# Triton.net
KiCad netlist of a schematic drawn in Altium Designer
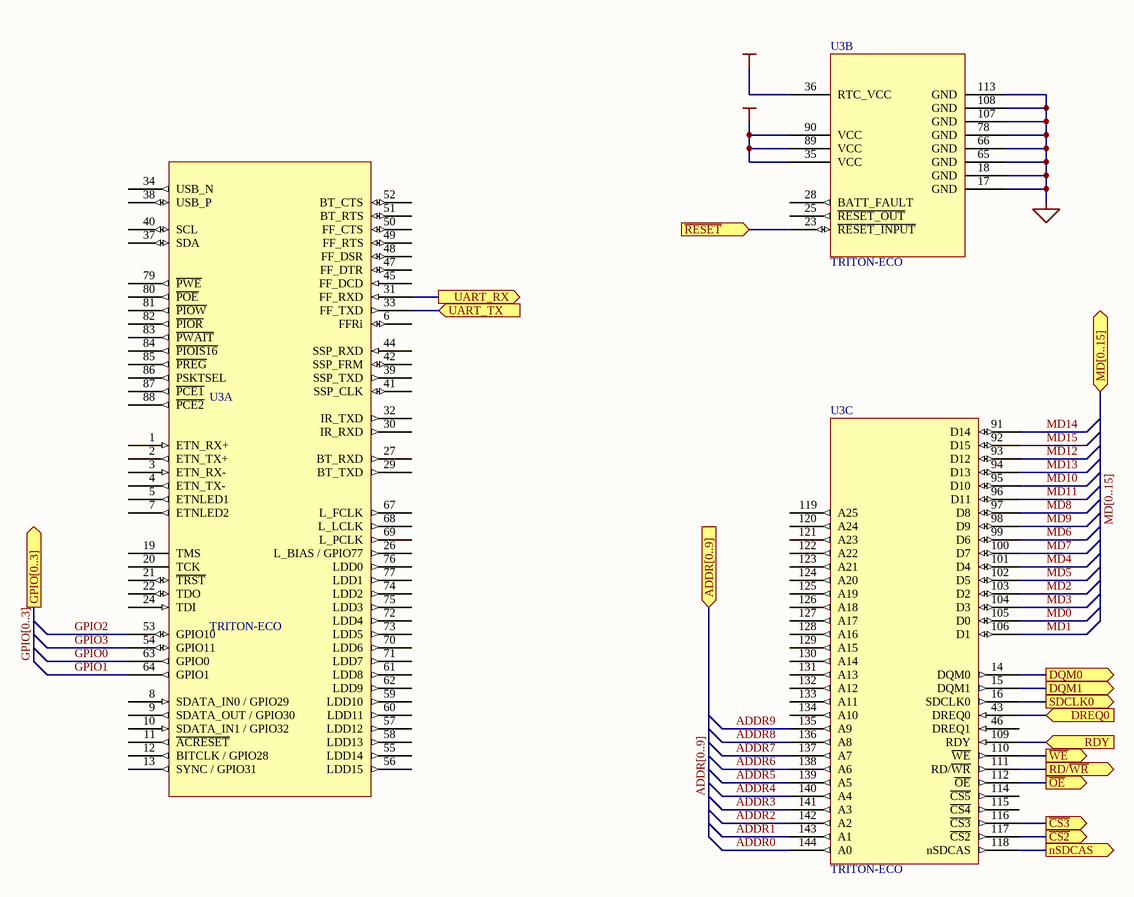
[diagram p0: Triton.SCHDOC]

(export (version "E")
  (design (tool "Eeschema 10.0.6"))
  (components
    (comp (ref "U3")
      (value "TRITON-ECO")
      (footprint "144-PIN SMT SODIMM")
      (description "Triton-ECO 400 MHz XScale DIMM")
      (libsource (lib "My devices") (part "TRITON_ECO"))
    )
  )
  (nets
    (net (code "1") (name "/ADDR0") (class "Default")
      (node (ref "U3") (pin "144") (pinfunction "A0_144") (pintype "output"))
    )
    (net (code "2") (name "/ADDR1") (class "Default")
      (node (ref "U3") (pin "143") (pinfunction "A1_143") (pintype "output"))
    )
    (net (code "3") (name "/ADDR2") (class "Default")
      (node (ref "U3") (pin "142") (pinfunction "A2_142") (pintype "output"))
    )
    (net (code "4") (name "/ADDR3") (class "Default")
      (node (ref "U3") (pin "141") (pinfunction "A3_141") (pintype "output"))
    )
    (net (code "5") (name "/ADDR4") (class "Default")
      (node (ref "U3") (pin "140") (pinfunction "A4_140") (pintype "output"))
    )
    (net (code "6") (name "/ADDR5") (class "Default")
      (node (ref "U3") (pin "139") (pinfunction "A5_139") (pintype "output"))
    )
    (net (code "7") (name "/ADDR6") (class "Default")
      (node (ref "U3") (pin "138") (pinfunction "A6_138") (pintype "output"))
    )
    (net (code "8") (name "/ADDR7") (class "Default")
      (node (ref "U3") (pin "137") (pinfunction "A7_137") (pintype "output"))
    )
    (net (code "9") (name "/ADDR8") (class "Default")
      (node (ref "U3") (pin "136") (pinfunction "A8_136") (pintype "output"))
    )
    (net (code "10") (name "/ADDR9") (class "Default")
      (node (ref "U3") (pin "135") (pinfunction "A9_135") (pintype "output"))
    )
    (net (code "12") (name "/DQM0") (class "Default")
      (node (ref "U3") (pin "14") (pinfunction "DQM0_14") (pintype "output"))
    )
    (net (code "13") (name "/DQM1") (class "Default")
      (node (ref "U3") (pin "15") (pinfunction "DQM1_15") (pintype "output"))
    )
    (net (code "14") (name "/DREQ0") (class "Default")
      (node (ref "U3") (pin "43") (pinfunction "DREQ0_43") (pintype "input"))
    )
    (net (code "15") (name "/GPIO0") (class "Default")
      (node (ref "U3") (pin "63") (pinfunction "GPIO0_63") (pintype "output"))
    )
    (net (code "16") (name "/GPIO1") (class "Default")
      (node (ref "U3") (pin "64") (pinfunction "GPIO1_64") (pintype "output"))
    )
    (net (code "17") (name "/GPIO2") (class "Default")
      (node (ref "U3") (pin "53") (pinfunction "GPIO10_53") (pintype "bidirectional"))
    )
    (net (code "18") (name "/GPIO3") (class "Default")
      (node (ref "U3") (pin "54") (pinfunction "GPIO11_54") (pintype "bidirectional"))
    )
    (net (code "20") (name "/MD0") (class "Default")
      (node (ref "U3") (pin "105") (pinfunction "D0_105") (pintype "bidirectional"))
    )
    (net (code "21") (name "/MD1") (class "Default")
      (node (ref "U3") (pin "106") (pinfunction "D1_106") (pintype "bidirectional"))
    )
    (net (code "22") (name "/MD2") (class "Default")
      (node (ref "U3") (pin "103") (pinfunction "D2_103") (pintype "bidirectional"))
    )
    (net (code "23") (name "/MD3") (class "Default")
      (node (ref "U3") (pin "104") (pinfunction "D3_104") (pintype "bidirectional"))
    )
    (net (code "24") (name "/MD4") (class "Default")
      (node (ref "U3") (pin "101") (pinfunction "D4_101") (pintype "bidirectional"))
    )
    (net (code "25") (name "/MD5") (class "Default")
      (node (ref "U3") (pin "102") (pinfunction "D5_102") (pintype "bidirectional"))
    )
    (net (code "26") (name "/MD6") (class "Default")
      (node (ref "U3") (pin "99") (pinfunction "D6_99") (pintype "bidirectional"))
    )
    (net (code "27") (name "/MD7") (class "Default")
      (node (ref "U3") (pin "100") (pinfunction "D7_100") (pintype "bidirectional"))
    )
    (net (code "28") (name "/MD8") (class "Default")
      (node (ref "U3") (pin "97") (pinfunction "D8_97") (pintype "bidirectional"))
    )
    (net (code "29") (name "/MD9") (class "Default")
      (node (ref "U3") (pin "98") (pinfunction "D9_98") (pintype "bidirectional"))
    )
    (net (code "30") (name "/MD10") (class "Default")
      (node (ref "U3") (pin "95") (pinfunction "D10_95") (pintype "bidirectional"))
    )
    (net (code "31") (name "/MD11") (class "Default")
      (node (ref "U3") (pin "96") (pinfunction "D11_96") (pintype "bidirectional"))
    )
    (net (code "32") (name "/MD12") (class "Default")
      (node (ref "U3") (pin "93") (pinfunction "D12_93") (pintype "bidirectional"))
    )
    (net (code "33") (name "/MD13") (class "Default")
      (node (ref "U3") (pin "94") (pinfunction "D13_94") (pintype "bidirectional"))
    )
    (net (code "34") (name "/MD14") (class "Default")
      (node (ref "U3") (pin "91") (pinfunction "D14_91") (pintype "bidirectional"))
    )
    (net (code "35") (name "/MD15") (class "Default")
      (node (ref "U3") (pin "92") (pinfunction "D15_92") (pintype "bidirectional"))
    )
    (net (code "37") (name "/RDY") (class "Default")
      (node (ref "U3") (pin "109") (pinfunction "RDY_109") (pintype "input"))
    )
    (net (code "38") (name "/RD{slash}~{WR}") (class "Default")
      (node (ref "U3") (pin "111") (pinfunction "RD/~{WR}_111") (pintype "output"))
    )
    (net (code "39") (name "/SDCLK0") (class "Default")
      (node (ref "U3") (pin "16") (pinfunction "SDCLK0_16") (pintype "output"))
    )
    (net (code "40") (name "/UART_RX") (class "Default")
      (node (ref "U3") (pin "31") (pinfunction "FF_RXD_31") (pintype "input"))
    )
    (net (code "41") (name "/UART_TX") (class "Default")
      (node (ref "U3") (pin "33") (pinfunction "FF_TXD_33") (pintype "output"))
    )
    (net (code "42") (name "/nSDCAS") (class "Default")
      (node (ref "U3") (pin "118") (pinfunction "nSDCAS_118") (pintype "output"))
    )
    (net (code "43") (name "/~{CS2}") (class "Default")
      (node (ref "U3") (pin "117") (pinfunction "~{CS2}_117") (pintype "output"))
    )
    (net (code "44") (name "/~{CS3}") (class "Default")
      (node (ref "U3") (pin "116") (pinfunction "~{CS3}_116") (pintype "output"))
    )
    (net (code "45") (name "/~{OE}") (class "Default")
      (node (ref "U3") (pin "112") (pinfunction "~{OE}_112") (pintype "output"))
    )
    (net (code "46") (name "/~{RESET}") (class "Default")
      (node (ref "U3") (pin "23") (pinfunction "~{RESET_INPUT}_23") (pintype "bidirectional"))
    )
    (net (code "47") (name "/~{WE}") (class "Default")
      (node (ref "U3") (pin "110") (pinfunction "~{WE}_110") (pintype "output"))
    )
    (net (code "48") (name "GND") (class "Default")
      (node (ref "U3") (pin "107") (pinfunction "GND_107") (pintype "power_in"))
      (node (ref "U3") (pin "108") (pinfunction "GND_108") (pintype "power_in"))
      (node (ref "U3") (pin "113") (pinfunction "GND_113") (pintype "power_in"))
      (node (ref "U3") (pin "17") (pinfunction "GND_17") (pintype "power_in"))
      (node (ref "U3") (pin "18") (pinfunction "GND_18") (pintype "power_in"))
      (node (ref "U3") (pin "65") (pinfunction "GND_65") (pintype "power_in"))
      (node (ref "U3") (pin "66") (pinfunction "GND_66") (pintype "power_in"))
      (node (ref "U3") (pin "78") (pinfunction "GND_78") (pintype "power_in"))
    )
    (net (code "49") (name "VCC") (class "Default")
      (node (ref "U3") (pin "35") (pinfunction "VCC_35") (pintype "power_in"))
      (node (ref "U3") (pin "36") (pinfunction "RTC_VCC_36") (pintype "power_in"))
      (node (ref "U3") (pin "89") (pinfunction "VCC_89") (pintype "power_in"))
      (node (ref "U3") (pin "90") (pinfunction "VCC_90") (pintype "power_in"))
    )
    (net (code "50") (name "unconnected-(U3A-BITCLK_{slash}_GPIO28-Pad12)") (class "Default")
      (node (ref "U3") (pin "12") (pinfunction "BITCLK_/_GPIO28_12") (pintype "output"))
    )
    (net (code "51") (name "unconnected-(U3A-BT_CTS-Pad52)") (class "Default")
      (node (ref "U3") (pin "52") (pinfunction "BT_CTS_52") (pintype "bidirectional"))
    )
    (net (code "52") (name "unconnected-(U3A-BT_RTS-Pad51)") (class "Default")
      (node (ref "U3") (pin "51") (pinfunction "BT_RTS_51") (pintype "bidirectional"))
    )
    (net (code "53") (name "unconnected-(U3A-BT_RXD-Pad27)") (class "Default")
      (node (ref "U3") (pin "27") (pinfunction "BT_RXD_27") (pintype "output"))
    )
    (net (code "54") (name "unconnected-(U3A-BT_TXD-Pad29)") (class "Default")
      (node (ref "U3") (pin "29") (pinfunction "BT_TXD_29") (pintype "output"))
    )
    (net (code "55") (name "unconnected-(U3A-ETNLED1-Pad5)") (class "Default")
      (node (ref "U3") (pin "5") (pinfunction "ETNLED1_5") (pintype "output"))
    )
    (net (code "56") (name "unconnected-(U3A-ETNLED2-Pad7)") (class "Default")
      (node (ref "U3") (pin "7") (pinfunction "ETNLED2_7") (pintype "output"))
    )
    (net (code "57") (name "unconnected-(U3A-ETN_RX+-Pad1)") (class "Default")
      (node (ref "U3") (pin "1") (pinfunction "ETN_RX+_1") (pintype "input"))
    )
    (net (code "58") (name "unconnected-(U3A-ETN_RX--Pad3)") (class "Default")
      (node (ref "U3") (pin "3") (pinfunction "ETN_RX-_3") (pintype "input"))
    )
    (net (code "59") (name "unconnected-(U3A-ETN_TX+-Pad2)") (class "Default")
      (node (ref "U3") (pin "2") (pinfunction "ETN_TX+_2") (pintype "output"))
    )
    (net (code "60") (name "unconnected-(U3A-ETN_TX--Pad4)") (class "Default")
      (node (ref "U3") (pin "4") (pinfunction "ETN_TX-_4") (pintype "output"))
    )
    (net (code "61") (name "unconnected-(U3A-FFRi-Pad6)") (class "Default")
      (node (ref "U3") (pin "6") (pinfunction "FFRi_6") (pintype "bidirectional"))
    )
    (net (code "62") (name "unconnected-(U3A-FF_CTS-Pad50)") (class "Default")
      (node (ref "U3") (pin "50") (pinfunction "FF_CTS_50") (pintype "bidirectional"))
    )
    (net (code "63") (name "unconnected-(U3A-FF_DCD-Pad45)") (class "Default")
      (node (ref "U3") (pin "45") (pinfunction "FF_DCD_45") (pintype "input"))
    )
    (net (code "64") (name "unconnected-(U3A-FF_DSR-Pad48)") (class "Default")
      (node (ref "U3") (pin "48") (pinfunction "FF_DSR_48") (pintype "bidirectional"))
    )
    (net (code "65") (name "unconnected-(U3A-FF_DTR-Pad47)") (class "Default")
      (node (ref "U3") (pin "47") (pinfunction "FF_DTR_47") (pintype "bidirectional"))
    )
    (net (code "66") (name "unconnected-(U3A-FF_RTS-Pad49)") (class "Default")
      (node (ref "U3") (pin "49") (pinfunction "FF_RTS_49") (pintype "bidirectional"))
    )
    (net (code "67") (name "unconnected-(U3A-IR_RXD-Pad30)") (class "Default")
      (node (ref "U3") (pin "30") (pinfunction "IR_RXD_30") (pintype "output"))
    )
    (net (code "68") (name "unconnected-(U3A-IR_TXD-Pad32)") (class "Default")
      (node (ref "U3") (pin "32") (pinfunction "IR_TXD_32") (pintype "output"))
    )
    (net (code "69") (name "unconnected-(U3A-LDD0-Pad76)") (class "Default")
      (node (ref "U3") (pin "76") (pinfunction "LDD0_76") (pintype "output"))
    )
    (net (code "70") (name "unconnected-(U3A-LDD1-Pad77)") (class "Default")
      (node (ref "U3") (pin "77") (pinfunction "LDD1_77") (pintype "output"))
    )
    (net (code "71") (name "unconnected-(U3A-LDD2-Pad74)") (class "Default")
      (node (ref "U3") (pin "74") (pinfunction "LDD2_74") (pintype "output"))
    )
    (net (code "72") (name "unconnected-(U3A-LDD3-Pad75)") (class "Default")
      (node (ref "U3") (pin "75") (pinfunction "LDD3_75") (pintype "output"))
    )
    (net (code "73") (name "unconnected-(U3A-LDD4-Pad72)") (class "Default")
      (node (ref "U3") (pin "72") (pinfunction "LDD4_72") (pintype "output"))
    )
    (net (code "74") (name "unconnected-(U3A-LDD5-Pad73)") (class "Default")
      (node (ref "U3") (pin "73") (pinfunction "LDD5_73") (pintype "output"))
    )
    (net (code "75") (name "unconnected-(U3A-LDD6-Pad70)") (class "Default")
      (node (ref "U3") (pin "70") (pinfunction "LDD6_70") (pintype "output"))
    )
    (net (code "76") (name "unconnected-(U3A-LDD7-Pad71)") (class "Default")
      (node (ref "U3") (pin "71") (pinfunction "LDD7_71") (pintype "output"))
    )
    (net (code "77") (name "unconnected-(U3A-LDD8-Pad61)") (class "Default")
      (node (ref "U3") (pin "61") (pinfunction "LDD8_61") (pintype "output"))
    )
    (net (code "78") (name "unconnected-(U3A-LDD9-Pad62)") (class "Default")
      (node (ref "U3") (pin "62") (pinfunction "LDD9_62") (pintype "output"))
    )
    (net (code "79") (name "unconnected-(U3A-LDD10-Pad59)") (class "Default")
      (node (ref "U3") (pin "59") (pinfunction "LDD10_59") (pintype "output"))
    )
    (net (code "80") (name "unconnected-(U3A-LDD11-Pad60)") (class "Default")
      (node (ref "U3") (pin "60") (pinfunction "LDD11_60") (pintype "output"))
    )
    (net (code "81") (name "unconnected-(U3A-LDD12-Pad57)") (class "Default")
      (node (ref "U3") (pin "57") (pinfunction "LDD12_57") (pintype "output"))
    )
    (net (code "82") (name "unconnected-(U3A-LDD13-Pad58)") (class "Default")
      (node (ref "U3") (pin "58") (pinfunction "LDD13_58") (pintype "output"))
    )
    (net (code "83") (name "unconnected-(U3A-LDD14-Pad55)") (class "Default")
      (node (ref "U3") (pin "55") (pinfunction "LDD14_55") (pintype "output"))
    )
    (net (code "84") (name "unconnected-(U3A-LDD15-Pad56)") (class "Default")
      (node (ref "U3") (pin "56") (pinfunction "LDD15_56") (pintype "output"))
    )
    (net (code "85") (name "unconnected-(U3A-L_BIAS_{slash}_GPIO77-Pad26)") (class "Default")
      (node (ref "U3") (pin "26") (pinfunction "L_BIAS_/_GPIO77_26") (pintype "output"))
    )
    (net (code "86") (name "unconnected-(U3A-L_FCLK-Pad67)") (class "Default")
      (node (ref "U3") (pin "67") (pinfunction "L_FCLK_67") (pintype "output"))
    )
    (net (code "87") (name "unconnected-(U3A-L_LCLK-Pad68)") (class "Default")
      (node (ref "U3") (pin "68") (pinfunction "L_LCLK_68") (pintype "output"))
    )
    (net (code "88") (name "unconnected-(U3A-L_PCLK-Pad69)") (class "Default")
      (node (ref "U3") (pin "69") (pinfunction "L_PCLK_69") (pintype "output"))
    )
    (net (code "89") (name "unconnected-(U3A-PSKTSEL-Pad86)") (class "Default")
      (node (ref "U3") (pin "86") (pinfunction "PSKTSEL_86") (pintype "output"))
    )
    (net (code "90") (name "unconnected-(U3A-SCL-Pad40)") (class "Default")
      (node (ref "U3") (pin "40") (pinfunction "SCL_40") (pintype "bidirectional"))
    )
    (net (code "91") (name "unconnected-(U3A-SDA-Pad37)") (class "Default")
      (node (ref "U3") (pin "37") (pinfunction "SDA_37") (pintype "bidirectional"))
    )
    (net (code "92") (name "unconnected-(U3A-SDATA_IN0_{slash}_GPIO29-Pad8)") (class "Default")
      (node (ref "U3") (pin "8") (pinfunction "SDATA_IN0_/_GPIO29_8") (pintype "input"))
    )
    (net (code "93") (name "unconnected-(U3A-SDATA_IN1_{slash}_GPIO32-Pad10)") (class "Default")
      (node (ref "U3") (pin "10") (pinfunction "SDATA_IN1_/_GPIO32_10") (pintype "input"))
    )
    (net (code "94") (name "unconnected-(U3A-SDATA_OUT_{slash}_GPIO30-Pad9)") (class "Default")
      (node (ref "U3") (pin "9") (pinfunction "SDATA_OUT_/_GPIO30_9") (pintype "output"))
    )
    (net (code "95") (name "unconnected-(U3A-SSP_CLK-Pad41)") (class "Default")
      (node (ref "U3") (pin "41") (pinfunction "SSP_CLK_41") (pintype "bidirectional"))
    )
    (net (code "96") (name "unconnected-(U3A-SSP_FRM-Pad42)") (class "Default")
      (node (ref "U3") (pin "42") (pinfunction "SSP_FRM_42") (pintype "bidirectional"))
    )
    (net (code "97") (name "unconnected-(U3A-SSP_RXD-Pad44)") (class "Default")
      (node (ref "U3") (pin "44") (pinfunction "SSP_RXD_44") (pintype "input"))
    )
    (net (code "98") (name "unconnected-(U3A-SSP_TXD-Pad39)") (class "Default")
      (node (ref "U3") (pin "39") (pinfunction "SSP_TXD_39") (pintype "output"))
    )
    (net (code "99") (name "unconnected-(U3A-SYNC_{slash}_GPIO31-Pad13)") (class "Default")
      (node (ref "U3") (pin "13") (pinfunction "SYNC_/_GPIO31_13") (pintype "output"))
    )
    (net (code "100") (name "unconnected-(U3A-TCK-Pad20)") (class "Default")
      (node (ref "U3") (pin "20") (pinfunction "TCK_20") (pintype "power_in"))
    )
    (net (code "101") (name "unconnected-(U3A-TDI-Pad24)") (class "Default")
      (node (ref "U3") (pin "24") (pinfunction "TDI_24") (pintype "input"))
    )
    (net (code "102") (name "unconnected-(U3A-TDO-Pad22)") (class "Default")
      (node (ref "U3") (pin "22") (pinfunction "TDO_22") (pintype "bidirectional"))
    )
    (net (code "103") (name "unconnected-(U3A-TMS-Pad19)") (class "Default")
      (node (ref "U3") (pin "19") (pinfunction "TMS_19") (pintype "power_in"))
    )
    (net (code "104") (name "unconnected-(U3A-USB_N-Pad34)") (class "Default")
      (node (ref "U3") (pin "34") (pinfunction "USB_N_34") (pintype "output"))
    )
    (net (code "105") (name "unconnected-(U3A-USB_P-Pad38)") (class "Default")
      (node (ref "U3") (pin "38") (pinfunction "USB_P_38") (pintype "bidirectional"))
    )
    (net (code "106") (name "unconnected-(U3A-~{ACRESET}-Pad11)") (class "Default")
      (node (ref "U3") (pin "11") (pinfunction "~{ACRESET}_11") (pintype "output"))
    )
    (net (code "107") (name "unconnected-(U3A-~{PCE1}-Pad87)") (class "Default")
      (node (ref "U3") (pin "87") (pinfunction "~{PCE1}_87") (pintype "output"))
    )
    (net (code "108") (name "unconnected-(U3A-~{PCE2}-Pad88)") (class "Default")
      (node (ref "U3") (pin "88") (pinfunction "~{PCE2}_88") (pintype "output"))
    )
    (net (code "109") (name "unconnected-(U3A-~{PIOIS16}-Pad84)") (class "Default")
      (node (ref "U3") (pin "84") (pinfunction "~{PIOIS16}_84") (pintype "output"))
    )
    (net (code "110") (name "unconnected-(U3A-~{PIOR}-Pad82)") (class "Default")
      (node (ref "U3") (pin "82") (pinfunction "~{PIOR}_82") (pintype "output"))
    )
    (net (code "111") (name "unconnected-(U3A-~{PIOW}-Pad81)") (class "Default")
      (node (ref "U3") (pin "81") (pinfunction "~{PIOW}_81") (pintype "output"))
    )
    (net (code "112") (name "unconnected-(U3A-~{POE}-Pad80)") (class "Default")
      (node (ref "U3") (pin "80") (pinfunction "~{POE}_80") (pintype "output"))
    )
    (net (code "113") (name "unconnected-(U3A-~{PREG}-Pad85)") (class "Default")
      (node (ref "U3") (pin "85") (pinfunction "~{PREG}_85") (pintype "output"))
    )
    (net (code "114") (name "unconnected-(U3A-~{PWAIT}-Pad83)") (class "Default")
      (node (ref "U3") (pin "83") (pinfunction "~{PWAIT}_83") (pintype "output"))
    )
    (net (code "115") (name "unconnected-(U3A-~{PWE}-Pad79)") (class "Default")
      (node (ref "U3") (pin "79") (pinfunction "~{PWE}_79") (pintype "output"))
    )
    (net (code "116") (name "unconnected-(U3A-~{TRST}-Pad21)") (class "Default")
      (node (ref "U3") (pin "21") (pinfunction "~{TRST}_21") (pintype "bidirectional"))
    )
    (net (code "117") (name "unconnected-(U3B-BATT_FAULT-Pad28)") (class "Default")
      (node (ref "U3") (pin "28") (pinfunction "BATT_FAULT_28") (pintype "output"))
    )
    (net (code "118") (name "unconnected-(U3B-~{RESET_OUT}-Pad25)") (class "Default")
      (node (ref "U3") (pin "25") (pinfunction "~{RESET_OUT}_25") (pintype "output"))
    )
    (net (code "119") (name "unconnected-(U3C-A10-Pad134)") (class "Default")
      (node (ref "U3") (pin "134") (pinfunction "A10_134") (pintype "output"))
    )
    (net (code "120") (name "unconnected-(U3C-A11-Pad133)") (class "Default")
      (node (ref "U3") (pin "133") (pinfunction "A11_133") (pintype "output"))
    )
    (net (code "121") (name "unconnected-(U3C-A12-Pad132)") (class "Default")
      (node (ref "U3") (pin "132") (pinfunction "A12_132") (pintype "output"))
    )
    (net (code "122") (name "unconnected-(U3C-A13-Pad131)") (class "Default")
      (node (ref "U3") (pin "131") (pinfunction "A13_131") (pintype "output"))
    )
    (net (code "123") (name "unconnected-(U3C-A14-Pad130)") (class "Default")
      (node (ref "U3") (pin "130") (pinfunction "A14_130") (pintype "output"))
    )
    (net (code "124") (name "unconnected-(U3C-A15-Pad129)") (class "Default")
      (node (ref "U3") (pin "129") (pinfunction "A15_129") (pintype "output"))
    )
    (net (code "125") (name "unconnected-(U3C-A16-Pad128)") (class "Default")
      (node (ref "U3") (pin "128") (pinfunction "A16_128") (pintype "output"))
    )
    (net (code "126") (name "unconnected-(U3C-A17-Pad127)") (class "Default")
      (node (ref "U3") (pin "127") (pinfunction "A17_127") (pintype "output"))
    )
    (net (code "127") (name "unconnected-(U3C-A18-Pad126)") (class "Default")
      (node (ref "U3") (pin "126") (pinfunction "A18_126") (pintype "output"))
    )
    (net (code "128") (name "unconnected-(U3C-A19-Pad125)") (class "Default")
      (node (ref "U3") (pin "125") (pinfunction "A19_125") (pintype "output"))
    )
    (net (code "129") (name "unconnected-(U3C-A20-Pad124)") (class "Default")
      (node (ref "U3") (pin "124") (pinfunction "A20_124") (pintype "output"))
    )
    (net (code "130") (name "unconnected-(U3C-A21-Pad123)") (class "Default")
      (node (ref "U3") (pin "123") (pinfunction "A21_123") (pintype "output"))
    )
    (net (code "131") (name "unconnected-(U3C-A22-Pad122)") (class "Default")
      (node (ref "U3") (pin "122") (pinfunction "A22_122") (pintype "output"))
    )
    (net (code "132") (name "unconnected-(U3C-A23-Pad121)") (class "Default")
      (node (ref "U3") (pin "121") (pinfunction "A23_121") (pintype "output"))
    )
    (net (code "133") (name "unconnected-(U3C-A24-Pad120)") (class "Default")
      (node (ref "U3") (pin "120") (pinfunction "A24_120") (pintype "output"))
    )
    (net (code "134") (name "unconnected-(U3C-A25-Pad119)") (class "Default")
      (node (ref "U3") (pin "119") (pinfunction "A25_119") (pintype "output"))
    )
    (net (code "135") (name "unconnected-(U3C-DREQ1-Pad46)") (class "Default")
      (node (ref "U3") (pin "46") (pinfunction "DREQ1_46") (pintype "input"))
    )
    (net (code "136") (name "unconnected-(U3C-~{CS4}-Pad115)") (class "Default")
      (node (ref "U3") (pin "115") (pinfunction "~{CS4}_115") (pintype "output"))
    )
    (net (code "137") (name "unconnected-(U3C-~{CS5}-Pad114)") (class "Default")
      (node (ref "U3") (pin "114") (pinfunction "~{CS5}_114") (pintype "output"))
    )
  )
)
